# 1Sens_lowPass.net
KiCad netlist of a schematic drawn in EAGLE
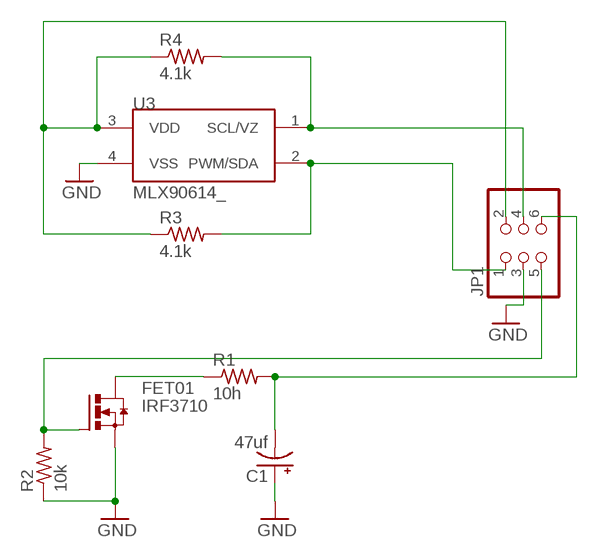
[diagram p0: schematic, sheet 1]

(export (version "E")
  (design (tool "Eeschema 10.0.6"))
  (components
    (comp (ref "C1")
      (value "47uf")
      (footprint "eagle-import:E2,5-6E")
      (libsource (lib "eagle-import") (part "CPOL-USE2,5-6E"))
    )
    (comp (ref "FET01")
      (value "IRF3710")
      (footprint "eagle-import:TO220AH")
      (libsource (lib "eagle-import") (part "IRF3704"))
    )
    (comp (ref "JP1")
      (value "PINHD-2X3")
      (footprint "eagle-import:2X03")
      (libsource (lib "eagle-import") (part "PINHD-2X3"))
    )
    (comp (ref "R1")
      (value "10h")
      (footprint "eagle-import:0207_7")
      (libsource (lib "eagle-import") (part "R-US_0207/7"))
    )
    (comp (ref "R2")
      (value "10k")
      (footprint "eagle-import:0207_7")
      (libsource (lib "eagle-import") (part "R-US_0207/7"))
    )
    (comp (ref "R3")
      (value "4.1k")
      (footprint "eagle-import:0204_5")
      (libsource (lib "eagle-import") (part "R-US_0204/5"))
    )
    (comp (ref "R4")
      (value "4.1k")
      (footprint "eagle-import:0204_5")
      (libsource (lib "eagle-import") (part "R-US_0204/5"))
    )
    (comp (ref "U3")
      (value "MLX90614_")
      (footprint "eagle-import:TO-39")
      (libsource (lib "eagle-import") (part "MLX90614_"))
    )
  )
  (nets
    (net (code "1") (name "GND") (class "Default")
      (node (ref "C1") (pin "+") (pinfunction "+_+") (pintype "passive"))
      (node (ref "FET01") (pin "E") (pinfunction "S_E") (pintype "passive"))
      (node (ref "JP1") (pin "3") (pinfunction "3_3") (pintype "passive"))
      (node (ref "R2") (pin "1") (pinfunction "1_1") (pintype "passive"))
      (node (ref "U3") (pin "4") (pinfunction "VSS_4") (pintype "bidirectional"))
    )
    (net (code "2") (name "Net-(C1-Pad-)") (class "Default")
      (node (ref "C1") (pin "-") (pinfunction "-_-") (pintype "passive"))
      (node (ref "JP1") (pin "6") (pinfunction "6_6") (pintype "passive"))
      (node (ref "R1") (pin "2") (pinfunction "2_2") (pintype "passive"))
    )
    (net (code "3") (name "Net-(FET01-D)") (class "Default")
      (node (ref "FET01") (pin "C") (pinfunction "D_C") (pintype "passive"))
      (node (ref "R1") (pin "1") (pinfunction "1_1") (pintype "passive"))
    )
    (net (code "4") (name "Net-(FET01-G)") (class "Default")
      (node (ref "FET01") (pin "B") (pinfunction "G_B") (pintype "passive"))
      (node (ref "JP1") (pin "5") (pinfunction "5_5") (pintype "passive"))
      (node (ref "R2") (pin "2") (pinfunction "2_2") (pintype "passive"))
    )
    (net (code "5") (name "Net-(U3-PWM{slash}SDA)") (class "Default")
      (node (ref "JP1") (pin "1") (pinfunction "1_1") (pintype "passive"))
      (node (ref "R3") (pin "2") (pinfunction "2_2") (pintype "passive"))
      (node (ref "U3") (pin "2") (pinfunction "PWM/SDA_2") (pintype "bidirectional"))
    )
    (net (code "6") (name "Net-(U3-SCL{slash}VZ)") (class "Default")
      (node (ref "JP1") (pin "4") (pinfunction "4_4") (pintype "passive"))
      (node (ref "R4") (pin "2") (pinfunction "2_2") (pintype "passive"))
      (node (ref "U3") (pin "1") (pinfunction "SCL/VZ_1") (pintype "bidirectional"))
    )
    (net (code "7") (name "Net-(U3-VDD)") (class "Default")
      (node (ref "JP1") (pin "2") (pinfunction "2_2") (pintype "passive"))
      (node (ref "R3") (pin "1") (pinfunction "1_1") (pintype "passive"))
      (node (ref "R4") (pin "1") (pinfunction "1_1") (pintype "passive"))
      (node (ref "U3") (pin "3") (pinfunction "VDD_3") (pintype "bidirectional"))
    )
  )
)
